# WiFi_Module.net
KiCad netlist of a schematic drawn in Altium Designer
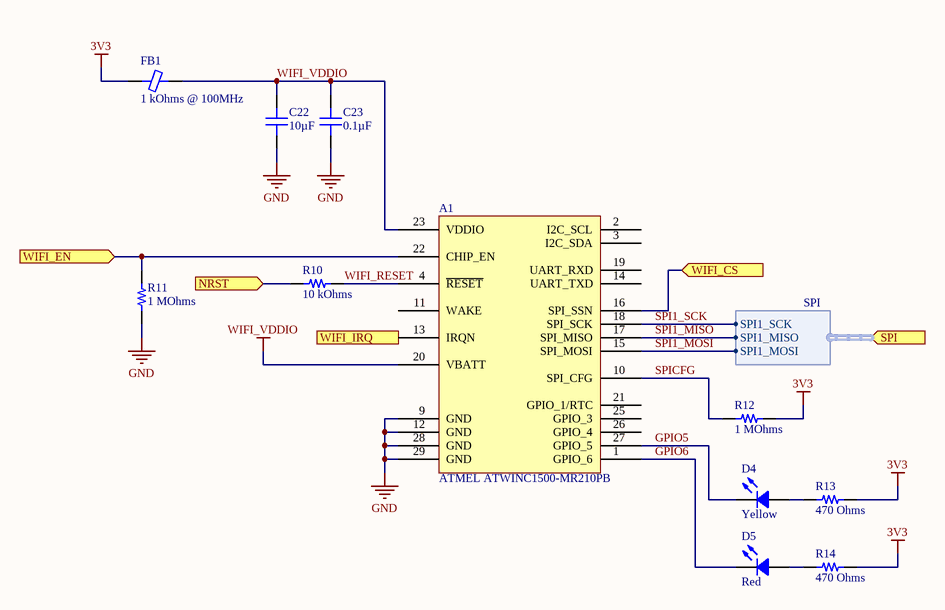
[diagram p0: WiFi Module.SchDoc]

(export (version "E")
  (design (tool "Eeschema 10.0.6"))
  (components
    (comp (ref "A1")
      (value "ATMEL ATWINC1500-MR210PB")
      (footprint "ATMEL ATWINC1500-MR210PB")
      (libsource (lib "SCH - RF - MODULE - ATMEL ATWINC1500-MR210PB") (part "ATMEL ATWINC1500-MR210PB"))
    )
    (comp (ref "C22")
      (value "10µF")
      (footprint "CAP 0805_2012")
      (description "CAP CER 10UF 10V X5R 0805")
      (fields
        (field (name "PART NUMBER") "CL21A106KPCLQNC")
        (field (name "MANUFACTURER") "Samsung Electro-Mechanics")
      )
      (libsource (lib "altiumlibrary.com") (part "Capacitor"))
    )
    (comp (ref "C23")
      (value "0.1µF")
      (footprint "CAP 0603_1608")
      (description "CAP CER 0.1UF 50V X7R 0603")
      (fields (field (name "PART NUMBER") "06035C104JAT4A") (field (name "MANUFACTURER") "AVX Corporation"))
      (libsource (lib "altiumlibrary.com") (part "Capacitor"))
    )
    (comp (ref "D4")
      (value "Yellow")
      (footprint "LED 1206_3216 YELLOW")
      (description "LED YELLOW CLEAR SMD")
      (fields (field (name "PART NUMBER") "AP3216SYCK") (field (name "MANUFACTURER") "Kingbright"))
      (libsource (lib "altiumlibrary.com") (part "LED"))
    )
    (comp (ref "D5")
      (value "Red")
      (footprint "LED 1206_3216 RED")
      (description "LED RED CLEAR CHIP SMD")
      (fields (field (name "PART NUMBER") "LTST-C21KRKT") (field (name "MANUFACTURER") "Lite-On Inc."))
      (libsource (lib "altiumlibrary.com") (part "LED"))
    )
    (comp (ref "FB1")
      (value "1 kOhms @ 100MHz")
      (footprint "FER 0805_2012")
      (description "FERRITE BEAD 1 KOHM 0805 1LN")
      (fields
        (field (name "PART NUMBER") "PE-0805FB102ST")
        (field (name "MANUFACTURER") "Pulse Electronics Network")
      )
      (libsource (lib "altiumlibrary.com") (part "Ferrite Chip"))
    )
    (comp (ref "R10")
      (value "10 kOhms")
      (footprint "RES 0603_1608")
      (description "RES SMD 10K OHM 5% 1/4W 0603")
      (fields
        (field (name "PART NUMBER") "ERJ-PA3J103V")
        (field (name "MANUFACTURER") "Panasonic Electronic Components")
      )
      (libsource (lib "altiumlibrary.com") (part "Resistor"))
    )
    (comp (ref "R11")
      (value "1 MOhms")
      (footprint "RES 0603_1608")
      (description "RES SMD 1M OHM 5% 1/4W 0603")
      (fields
        (field (name "PART NUMBER") "ERJ-PA3J105V")
        (field (name "MANUFACTURER") "Panasonic Electronic Components")
      )
      (libsource (lib "altiumlibrary.com") (part "Resistor"))
    )
    (comp (ref "R12")
      (value "1 MOhms")
      (footprint "RES 0603_1608")
      (description "RES SMD 1M OHM 5% 1/4W 0603")
      (fields
        (field (name "PART NUMBER") "ERJ-PA3J105V")
        (field (name "MANUFACTURER") "Panasonic Electronic Components")
      )
      (libsource (lib "altiumlibrary.com") (part "Resistor"))
    )
    (comp (ref "R13")
      (value "470 Ohms")
      (footprint "RES 0603_1608")
      (description "CRGCQ 0603 470R 5%")
      (fields
        (field (name "PART NUMBER") "CRGCQ0603J470R")
        (field (name "MANUFACTURER") "TE Connectivity Passive Product")
      )
      (libsource (lib "altiumlibrary.com") (part "Resistor"))
    )
    (comp (ref "R14")
      (value "470 Ohms")
      (footprint "RES 0603_1608")
      (description "CRGCQ 0603 470R 5%")
      (fields
        (field (name "PART NUMBER") "CRGCQ0603J470R")
        (field (name "MANUFACTURER") "TE Connectivity Passive Product")
      )
      (libsource (lib "altiumlibrary.com") (part "Resistor"))
    )
  )
  (nets
    (net (code "2") (name "/GPIO5") (class "Default")
      (node (ref "A1") (pin "27") (pinfunction "GPIO_5_27") (pintype "passive"))
      (node (ref "D4") (pin "2") (pinfunction "2_2") (pintype "passive"))
    )
    (net (code "3") (name "/GPIO6") (class "Default")
      (node (ref "A1") (pin "1") (pinfunction "GPIO_6_1") (pintype "passive"))
      (node (ref "D5") (pin "2") (pinfunction "2_2") (pintype "passive"))
    )
    (net (code "4") (name "/NRST") (class "Default")
      (node (ref "R10") (pin "1") (pinfunction "1_1") (pintype "passive"))
    )
    (net (code "5") (name "/SPI1_MISO") (class "Default")
      (node (ref "A1") (pin "17") (pinfunction "SPI_MISO_17") (pintype "passive"))
    )
    (net (code "6") (name "/SPI1_MOSI") (class "Default")
      (node (ref "A1") (pin "15") (pinfunction "SPI_MOSI_15") (pintype "passive"))
    )
    (net (code "7") (name "/SPI1_SCK") (class "Default")
      (node (ref "A1") (pin "18") (pinfunction "SPI_SCK_18") (pintype "passive"))
    )
    (net (code "8") (name "/SPICFG") (class "Default")
      (node (ref "A1") (pin "10") (pinfunction "SPI_CFG_10") (pintype "passive"))
      (node (ref "R12") (pin "1") (pinfunction "1_1") (pintype "passive"))
    )
    (net (code "9") (name "/WIFI_CS") (class "Default")
      (node (ref "A1") (pin "16") (pinfunction "SPI_SSN_16") (pintype "passive"))
    )
    (net (code "10") (name "/WIFI_EN") (class "Default")
      (node (ref "A1") (pin "22") (pinfunction "CHIP_EN_22") (pintype "passive"))
      (node (ref "R11") (pin "2") (pinfunction "2_2") (pintype "passive"))
    )
    (net (code "11") (name "/WIFI_IRQ") (class "Default")
      (node (ref "A1") (pin "13") (pinfunction "IRQN_13") (pintype "passive"))
    )
    (net (code "12") (name "/WIFI_RESET") (class "Default")
      (node (ref "A1") (pin "4") (pinfunction "~{RESET}_4") (pintype "passive"))
      (node (ref "R10") (pin "2") (pinfunction "2_2") (pintype "passive"))
    )
    (net (code "14") (name "3V3") (class "Default")
      (node (ref "FB1") (pin "1") (pinfunction "1_1") (pintype "passive"))
      (node (ref "R12") (pin "2") (pinfunction "2_2") (pintype "passive"))
      (node (ref "R13") (pin "2") (pinfunction "2_2") (pintype "passive"))
      (node (ref "R14") (pin "2") (pinfunction "2_2") (pintype "passive"))
    )
    (net (code "15") (name "GND") (class "Default")
      (node (ref "A1") (pin "12") (pinfunction "GND_12") (pintype "passive"))
      (node (ref "A1") (pin "28") (pinfunction "GND_28") (pintype "passive"))
      (node (ref "A1") (pin "29") (pinfunction "GND_29") (pintype "passive"))
      (node (ref "A1") (pin "9") (pinfunction "GND_9") (pintype "passive"))
      (node (ref "C22") (pin "1") (pinfunction "1_1") (pintype "passive"))
      (node (ref "C23") (pin "1") (pinfunction "1_1") (pintype "passive"))
      (node (ref "R11") (pin "1") (pinfunction "1_1") (pintype "passive"))
    )
    (net (code "16") (name "Net-(D4-Pad1)") (class "Default")
      (node (ref "D4") (pin "1") (pinfunction "1_1") (pintype "passive"))
      (node (ref "R13") (pin "1") (pinfunction "1_1") (pintype "passive"))
    )
    (net (code "17") (name "Net-(D5-Pad1)") (class "Default")
      (node (ref "D5") (pin "1") (pinfunction "1_1") (pintype "passive"))
      (node (ref "R14") (pin "1") (pinfunction "1_1") (pintype "passive"))
    )
    (net (code "18") (name "WIFI_VDDIO") (class "Default")
      (node (ref "A1") (pin "20") (pinfunction "VBATT_20") (pintype "passive"))
      (node (ref "A1") (pin "23") (pinfunction "VDDIO_23") (pintype "passive"))
      (node (ref "C22") (pin "2") (pinfunction "2_2") (pintype "passive"))
      (node (ref "C23") (pin "2") (pinfunction "2_2") (pintype "passive"))
      (node (ref "FB1") (pin "2") (pinfunction "2_2") (pintype "passive"))
    )
    (net (code "19") (name "unconnected-(A1-GPIO_1{slash}RTC-Pad21)") (class "Default")
      (node (ref "A1") (pin "21") (pinfunction "GPIO_1/RTC_21") (pintype "passive"))
    )
    (net (code "20") (name "unconnected-(A1-GPIO_3-Pad25)") (class "Default")
      (node (ref "A1") (pin "25") (pinfunction "GPIO_3_25") (pintype "passive"))
    )
    (net (code "21") (name "unconnected-(A1-GPIO_4-Pad26)") (class "Default")
      (node (ref "A1") (pin "26") (pinfunction "GPIO_4_26") (pintype "passive"))
    )
    (net (code "22") (name "unconnected-(A1-I2C_SCL-Pad2)") (class "Default")
      (node (ref "A1") (pin "2") (pinfunction "I2C_SCL_2") (pintype "passive"))
    )
    (net (code "23") (name "unconnected-(A1-I2C_SDA-Pad3)") (class "Default")
      (node (ref "A1") (pin "3") (pinfunction "I2C_SDA_3") (pintype "passive"))
    )
    (net (code "24") (name "unconnected-(A1-UART_RXD-Pad19)") (class "Default")
      (node (ref "A1") (pin "19") (pinfunction "UART_RXD_19") (pintype "passive"))
    )
    (net (code "25") (name "unconnected-(A1-UART_TXD-Pad14)") (class "Default")
      (node (ref "A1") (pin "14") (pinfunction "UART_TXD_14") (pintype "passive"))
    )
    (net (code "26") (name "unconnected-(A1-WAKE-Pad11)") (class "Default")
      (node (ref "A1") (pin "11") (pinfunction "WAKE_11") (pintype "passive"))
    )
  )
)
